# Module_MCU_ArduinoNano.net
KiCad netlist of a schematic drawn in EAGLE
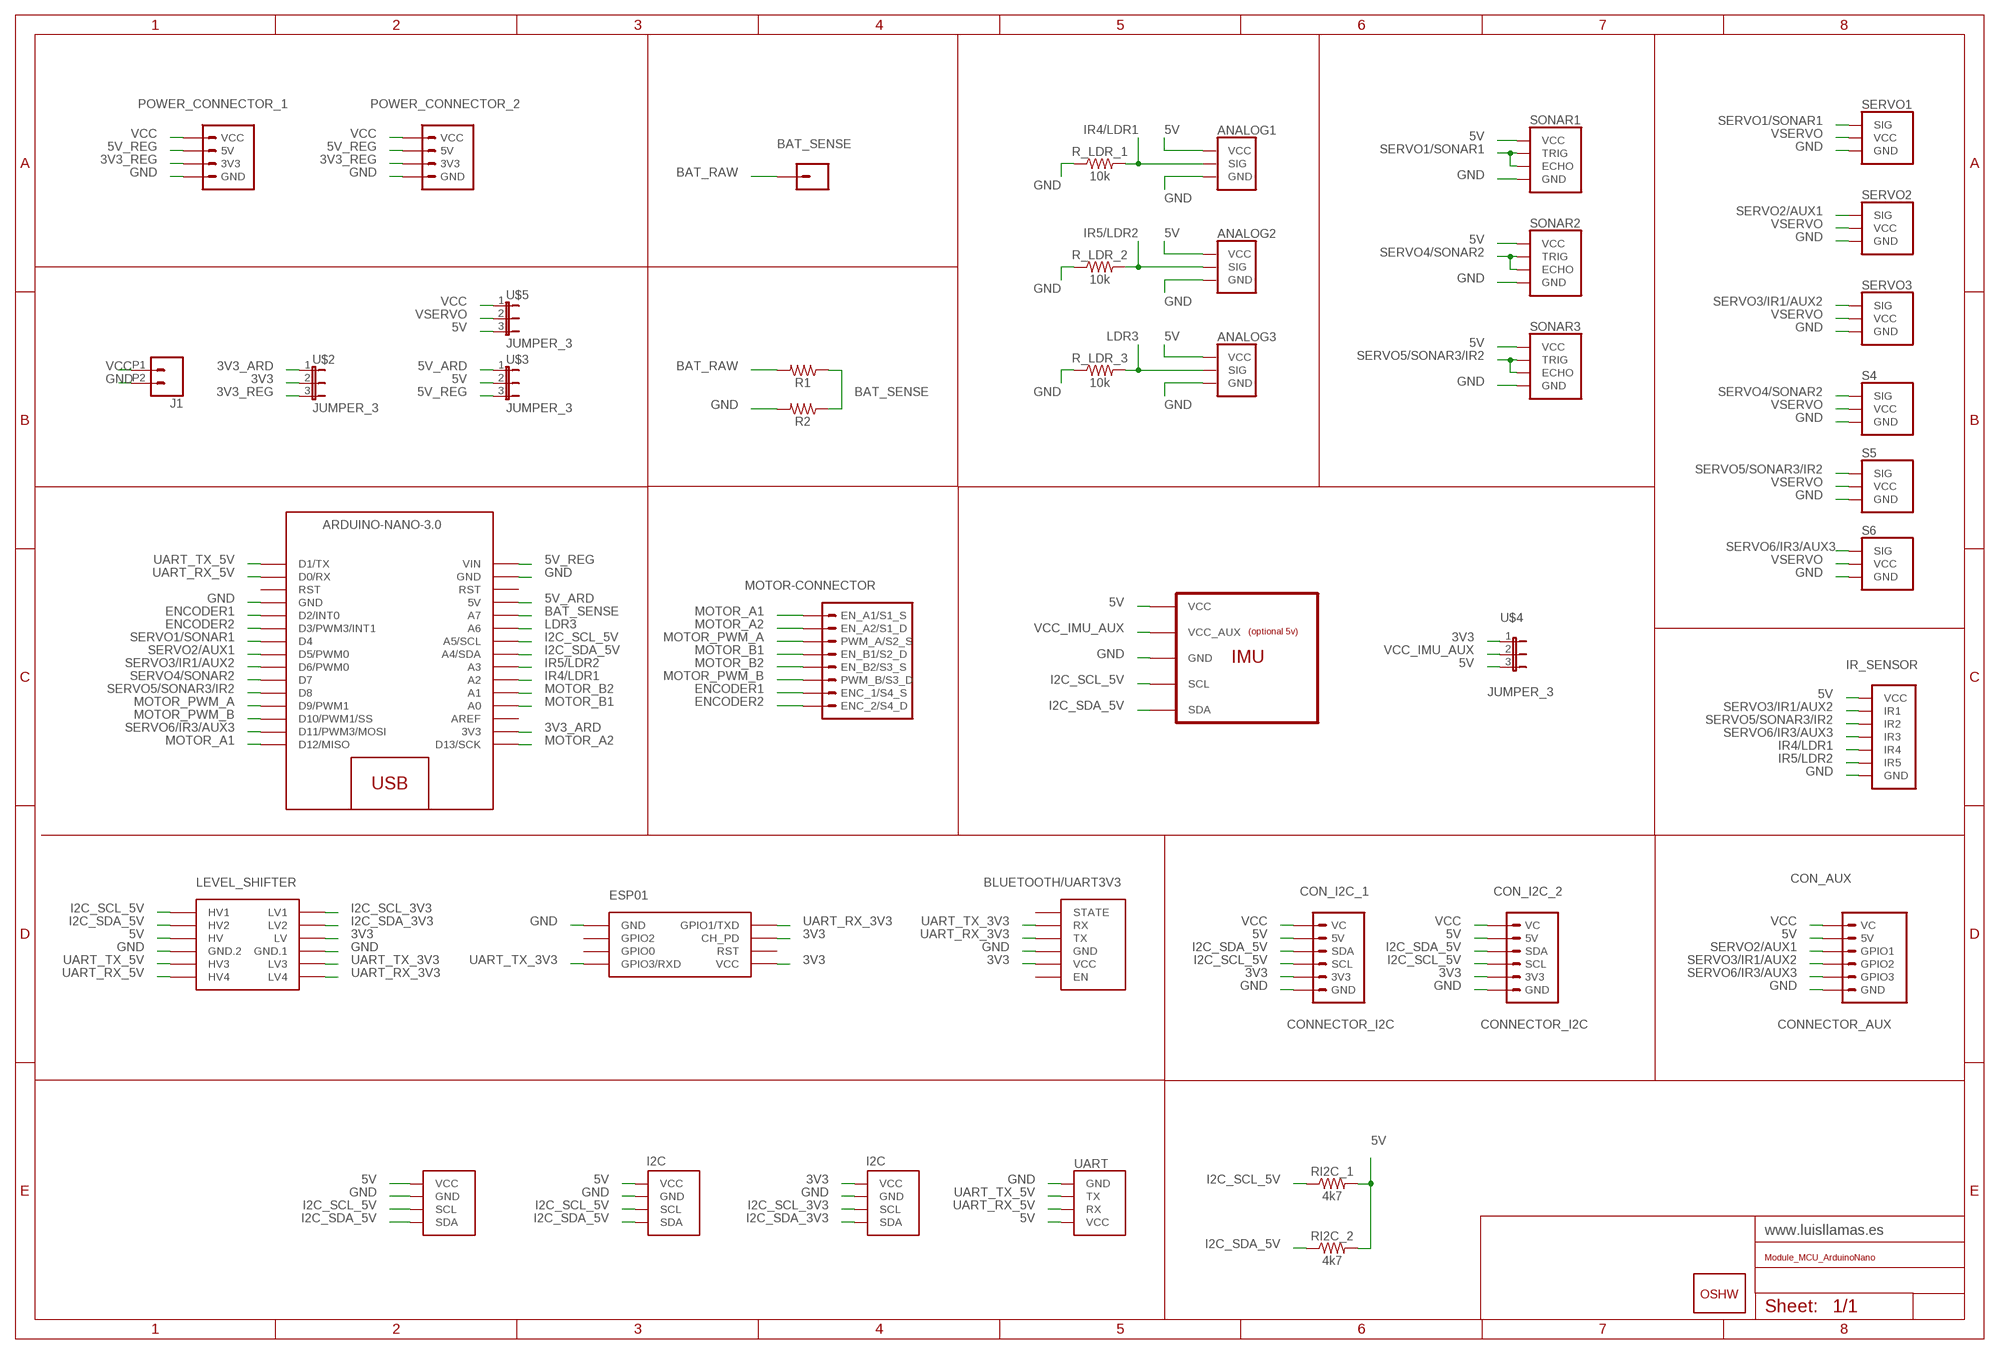
[diagram p0: schematic, sheet 1]

(export (version "E")
  (design (tool "Eeschema 10.0.6"))
  (components
    (comp (ref "ANALOG1")
      (value "LDR/OCT")
      (footprint "eagle-import:LDR")
      (libsource (lib "eagle-import") (part "LDR/OCT"))
    )
    (comp (ref "ANALOG2")
      (value "LDR/OCT")
      (footprint "eagle-import:LDR")
      (libsource (lib "eagle-import") (part "LDR/OCT"))
    )
    (comp (ref "ANALOG3")
      (value "LDR/OCT")
      (footprint "eagle-import:LDR")
      (libsource (lib "eagle-import") (part "LDR/OCT"))
    )
    (comp (ref "ARDUINO_NANO1")
      (value "ARDUINO-NANO-3.0")
      (footprint "eagle-import:ARDUINO-NANO-3.0")
      (libsource (lib "eagle-import") (part "ARDUINO-NANO-3.0"))
    )
    (comp (ref "BAT_SENSE")
      (value "CONN_01")
      (footprint "eagle-import:1X01")
      (libsource (lib "eagle-import") (part "CONN_01"))
    )
    (comp (ref "BLUETOOTH/UART3V3")
      (value "BLUETOOTH-HC-05")
      (footprint "eagle-import:BLUETOOTH-HC-05")
      (libsource (lib "eagle-import") (part "BLUETOOTH-HC-05"))
    )
    (comp (ref "CON_AUX")
      (value "CONNECTOR_AUX")
      (footprint "eagle-import:CONNECTOR_AUX")
      (libsource (lib "eagle-import") (part "CONNECTOR_AUX"))
    )
    (comp (ref "CON_I2C_1")
      (value "CONNECTOR_I2C")
      (footprint "eagle-import:CONNECTOR_I2C")
      (libsource (lib "eagle-import") (part "CONNECTOR_I2C"))
    )
    (comp (ref "CON_I2C_2")
      (value "CONNECTOR_I2C")
      (footprint "eagle-import:CONNECTOR_I2C")
      (libsource (lib "eagle-import") (part "CONNECTOR_I2C"))
    )
    (comp (ref "GOLD_ORB_SM1")
      (value "OSHWLOGO_GOLD_ORB_MED")
      (footprint "eagle-import:OSHW1")
      (libsource (lib "eagle-import") (part "OSHWLOGO_GOLD_ORB_MED"))
    )
    (comp (ref "I2C_1")
      (value "I2C")
      (footprint "eagle-import:I2C_VCC_GND_SCL_SDA")
      (libsource (lib "eagle-import") (part "GENERIC_I2CVCC_GND_SCL_SDA"))
    )
    (comp (ref "I2C_2")
      (value "GENERIC_I2CVCC_GND_SCL_SDA")
      (footprint "eagle-import:I2C_VCC_GND_SCL_SDA")
      (libsource (lib "eagle-import") (part "GENERIC_I2CVCC_GND_SCL_SDA"))
    )
    (comp (ref "I2C_3")
      (value "I2C")
      (footprint "eagle-import:I2C_VCC_GND_SCL_SDA")
      (libsource (lib "eagle-import") (part "GENERIC_I2CVCC_GND_SCL_SDA"))
    )
    (comp (ref "IR_SENSOR")
      (value "IR-5/OCT")
      (footprint "eagle-import:IR-5")
      (libsource (lib "eagle-import") (part "IR-5/OCT"))
    )
    (comp (ref "J1")
      (value "CONN_022.54MM_SCREWTERM")
      (footprint "eagle-import:1X02_2.54_SCREWTERM")
      (libsource (lib "eagle-import") (part "CONN_022.54MM_SCREWTERM"))
    )
    (comp (ref "LEVEL_SHIFTER")
      (value "LEVEL-SHIFTER-4CH")
      (footprint "eagle-import:LEVEL-SHIFTER-4CH")
      (libsource (lib "eagle-import") (part "LEVEL-SHIFTER-4CH"))
    )
    (comp (ref "MOTOR_CONNECTOR")
      (value "MOTOR-CONNECTOR")
      (footprint "eagle-import:MOTOR-CONNECTOR")
      (libsource (lib "eagle-import") (part "MOTOR-CONNECTOR"))
    )
    (comp (ref "POWER_CONNECTOR_1")
      (value "POWER-CONNECTOR")
      (footprint "eagle-import:POWER-CONNECTOR")
      (libsource (lib "eagle-import") (part "POWER-CONNECTOR"))
    )
    (comp (ref "POWER_CONNECTOR_2")
      (value "POWER-CONNECTOR")
      (footprint "eagle-import:POWER-CONNECTOR")
      (libsource (lib "eagle-import") (part "POWER-CONNECTOR"))
    )
    (comp (ref "R1")
      (value "RESISTOR1206")
      (footprint "eagle-import:1206")
      (libsource (lib "eagle-import") (part "RESISTOR1206"))
    )
    (comp (ref "R2")
      (value "RESISTOR1206")
      (footprint "eagle-import:1206")
      (libsource (lib "eagle-import") (part "RESISTOR1206"))
    )
    (comp (ref "RI2C_1")
      (value "4k7")
      (footprint "eagle-import:1206")
      (libsource (lib "eagle-import") (part "RESISTOR1206"))
    )
    (comp (ref "RI2C_2")
      (value "4k7")
      (footprint "eagle-import:1206")
      (libsource (lib "eagle-import") (part "RESISTOR1206"))
    )
    (comp (ref "R_LDR_1")
      (value "10k")
      (footprint "eagle-import:1206")
      (libsource (lib "eagle-import") (part "RESISTOR1206"))
    )
    (comp (ref "R_LDR_2")
      (value "10k")
      (footprint "eagle-import:1206")
      (libsource (lib "eagle-import") (part "RESISTOR1206"))
    )
    (comp (ref "R_LDR_3")
      (value "10k")
      (footprint "eagle-import:1206")
      (libsource (lib "eagle-import") (part "RESISTOR1206"))
    )
    (comp (ref "S4")
      (value "SERVOSERVO")
      (footprint "eagle-import:SERVO")
      (libsource (lib "eagle-import") (part "SERVOSERVO"))
    )
    (comp (ref "S5")
      (value "SERVOSERVO")
      (footprint "eagle-import:SERVO")
      (libsource (lib "eagle-import") (part "SERVOSERVO"))
    )
    (comp (ref "S6")
      (value "SERVOSERVO")
      (footprint "eagle-import:SERVO")
      (libsource (lib "eagle-import") (part "SERVOSERVO"))
    )
    (comp (ref "SERVO1")
      (value "SERVOSERVO")
      (footprint "eagle-import:SERVO")
      (libsource (lib "eagle-import") (part "SERVOSERVO"))
    )
    (comp (ref "SERVO2")
      (value "SERVOSERVO")
      (footprint "eagle-import:SERVO")
      (libsource (lib "eagle-import") (part "SERVOSERVO"))
    )
    (comp (ref "SERVO3")
      (value "SERVOSERVO")
      (footprint "eagle-import:SERVO")
      (libsource (lib "eagle-import") (part "SERVOSERVO"))
    )
    (comp (ref "SONAR1")
      (value "ULTRASONIC/OCT")
      (footprint "eagle-import:ULTRASONIC")
      (libsource (lib "eagle-import") (part "ULTRASONIC/OCT"))
    )
    (comp (ref "SONAR2")
      (value "ULTRASONIC/OCT")
      (footprint "eagle-import:ULTRASONIC")
      (libsource (lib "eagle-import") (part "ULTRASONIC/OCT"))
    )
    (comp (ref "SONAR3")
      (value "ULTRASONIC/OCT")
      (footprint "eagle-import:ULTRASONIC")
      (libsource (lib "eagle-import") (part "ULTRASONIC/OCT"))
    )
    (comp (ref "U$1")
      (value "ESP01")
      (footprint "eagle-import:ESP01")
      (libsource (lib "eagle-import") (part "ESP01"))
    )
    (comp (ref "U$2")
      (value "JUMPER_3")
      (footprint "eagle-import:JUMPER_3")
      (libsource (lib "eagle-import") (part "JUMPER_3"))
    )
    (comp (ref "U$3")
      (value "JUMPER_3")
      (footprint "eagle-import:JUMPER_3")
      (libsource (lib "eagle-import") (part "JUMPER_3"))
    )
    (comp (ref "U$4")
      (value "JUMPER_3")
      (footprint "eagle-import:JUMPER_3")
      (libsource (lib "eagle-import") (part "JUMPER_3"))
    )
    (comp (ref "U$5")
      (value "JUMPER_3")
      (footprint "eagle-import:JUMPER_3")
      (libsource (lib "eagle-import") (part "JUMPER_3"))
    )
    (comp (ref "U1")
      (value "IMU_6/9/10DOFMPU6050")
      (footprint "eagle-import:IMU_6_9_10DOF")
      (libsource (lib "eagle-import") (part "IMU_6/9/10DOFMPU6050"))
    )
    (comp (ref "UART")
      (value "UART")
      (footprint "eagle-import:GENERIC_UART")
      (libsource (lib "eagle-import") (part "GENERIC_UARTGND_TX_RX_VCC"))
    )
  )
  (nets
    (net (code "1") (name "/3V3") (class "Default")
      (node (ref "BLUETOOTH/UART3V3") (pin "VCC") (pinfunction "VCC_VCC") (pintype "power_in"))
      (node (ref "CON_I2C_1") (pin "3V3") (pinfunction "3V3_3V3") (pintype "passive"))
      (node (ref "CON_I2C_2") (pin "3V3") (pinfunction "3V3_3V3") (pintype "passive"))
      (node (ref "I2C_3") (pin "VCC") (pinfunction "VCC_VCC") (pintype "power_in"))
      (node (ref "LEVEL_SHIFTER") (pin "J1.3") (pinfunction "LV_J1.3") (pintype "power_in"))
      (node (ref "U$1") (pin "CH_PD") (pinfunction "CH_PD_CH_PD") (pintype "bidirectional"))
      (node (ref "U$1") (pin "VCC") (pinfunction "VCC_VCC") (pintype "power_in"))
      (node (ref "U$2") (pin "2") (pinfunction "2_2") (pintype "passive"))
      (node (ref "U$4") (pin "1") (pinfunction "1_1") (pintype "passive"))
    )
    (net (code "2") (name "/3V3_ARD") (class "Default")
      (node (ref "ARDUINO_NANO1") (pin "3V3") (pinfunction "3V3_3V3") (pintype "power_in"))
      (node (ref "U$2") (pin "1") (pinfunction "1_1") (pintype "passive"))
    )
    (net (code "3") (name "/3V3_REG") (class "Default")
      (node (ref "POWER_CONNECTOR_1") (pin "3V3") (pinfunction "3V3_3V3") (pintype "passive"))
      (node (ref "POWER_CONNECTOR_2") (pin "3V3") (pinfunction "3V3_3V3") (pintype "passive"))
      (node (ref "U$2") (pin "3") (pinfunction "3_3") (pintype "passive"))
    )
    (net (code "4") (name "/5V") (class "Default")
      (node (ref "ANALOG1") (pin "VCC") (pinfunction "VCC_VCC") (pintype "power_in"))
      (node (ref "ANALOG2") (pin "VCC") (pinfunction "VCC_VCC") (pintype "power_in"))
      (node (ref "ANALOG3") (pin "VCC") (pinfunction "VCC_VCC") (pintype "power_in"))
      (node (ref "CON_AUX") (pin "5V") (pinfunction "5V_5V") (pintype "passive"))
      (node (ref "CON_I2C_1") (pin "5V") (pinfunction "5V_5V") (pintype "passive"))
      (node (ref "CON_I2C_2") (pin "5V") (pinfunction "5V_5V") (pintype "passive"))
      (node (ref "I2C_1") (pin "VCC") (pinfunction "VCC_VCC") (pintype "power_in"))
      (node (ref "I2C_2") (pin "VCC") (pinfunction "VCC_VCC") (pintype "power_in"))
      (node (ref "IR_SENSOR") (pin "VCC") (pinfunction "VCC_VCC") (pintype "power_in"))
      (node (ref "LEVEL_SHIFTER") (pin "J2.3") (pinfunction "HV_J2.3") (pintype "power_in"))
      (node (ref "RI2C_1") (pin "2") (pinfunction "2_2") (pintype "passive"))
      (node (ref "RI2C_2") (pin "2") (pinfunction "2_2") (pintype "passive"))
      (node (ref "SONAR1") (pin "VCC") (pinfunction "VCC_VCC") (pintype "power_in"))
      (node (ref "SONAR2") (pin "VCC") (pinfunction "VCC_VCC") (pintype "power_in"))
      (node (ref "SONAR3") (pin "VCC") (pinfunction "VCC_VCC") (pintype "power_in"))
      (node (ref "U$3") (pin "2") (pinfunction "2_2") (pintype "passive"))
      (node (ref "U$4") (pin "3") (pinfunction "3_3") (pintype "passive"))
      (node (ref "U$5") (pin "3") (pinfunction "3_3") (pintype "passive"))
      (node (ref "U1") (pin "VCC") (pinfunction "VCC_VCC") (pintype "power_in"))
      (node (ref "UART") (pin "VCC") (pinfunction "VCC_VCC") (pintype "bidirectional"))
    )
    (net (code "5") (name "/5V_ARD") (class "Default")
      (node (ref "ARDUINO_NANO1") (pin "5V") (pinfunction "5V_5V") (pintype "bidirectional"))
      (node (ref "U$3") (pin "1") (pinfunction "1_1") (pintype "passive"))
    )
    (net (code "6") (name "/5V_REG") (class "Default")
      (node (ref "ARDUINO_NANO1") (pin "VIN") (pinfunction "VIN_VIN") (pintype "power_in"))
      (node (ref "POWER_CONNECTOR_1") (pin "5V") (pinfunction "5V_5V") (pintype "passive"))
      (node (ref "POWER_CONNECTOR_2") (pin "5V") (pinfunction "5V_5V") (pintype "passive"))
      (node (ref "U$3") (pin "3") (pinfunction "3_3") (pintype "passive"))
    )
    (net (code "7") (name "/BAT_RAW") (class "Default")
      (node (ref "BAT_SENSE") (pin "1") (pinfunction "1_1") (pintype "passive"))
      (node (ref "R1") (pin "2") (pinfunction "2_2") (pintype "passive"))
    )
    (net (code "8") (name "/BAT_SENSE") (class "Default")
      (node (ref "ARDUINO_NANO1") (pin "A7") (pinfunction "A7_A7") (pintype "bidirectional"))
      (node (ref "R1") (pin "1") (pinfunction "1_1") (pintype "passive"))
      (node (ref "R2") (pin "1") (pinfunction "1_1") (pintype "passive"))
    )
    (net (code "9") (name "/ENCODER1") (class "Default")
      (node (ref "ARDUINO_NANO1") (pin "D2") (pinfunction "D2/INT0_D2") (pintype "bidirectional"))
      (node (ref "MOTOR_CONNECTOR") (pin "ENC_1/S4_S") (pinfunction "ENC_1/S4_S_ENC_1/S4_S") (pintype "passive"))
    )
    (net (code "10") (name "/ENCODER2") (class "Default")
      (node (ref "ARDUINO_NANO1") (pin "D3") (pinfunction "D3/PWM3/INT1_D3") (pintype "bidirectional"))
      (node (ref "MOTOR_CONNECTOR") (pin "ENC_2/S4_D") (pinfunction "ENC_2/S4_D_ENC_2/S4_D") (pintype "passive"))
    )
    (net (code "11") (name "/GND") (class "Default")
      (node (ref "ANALOG1") (pin "GND") (pinfunction "GND_GND") (pintype "power_in"))
      (node (ref "ANALOG2") (pin "GND") (pinfunction "GND_GND") (pintype "power_in"))
      (node (ref "ANALOG3") (pin "GND") (pinfunction "GND_GND") (pintype "power_in"))
      (node (ref "ARDUINO_NANO1") (pin "GND@1") (pinfunction "GND_GND@1") (pintype "power_in"))
      (node (ref "ARDUINO_NANO1") (pin "GND@2") (pinfunction "GND_GND@2") (pintype "power_in"))
      (node (ref "BLUETOOTH/UART3V3") (pin "GND") (pinfunction "GND_GND") (pintype "power_in"))
      (node (ref "CON_AUX") (pin "GND") (pinfunction "GND_GND") (pintype "passive"))
      (node (ref "CON_I2C_1") (pin "GND") (pinfunction "GND_GND") (pintype "passive"))
      (node (ref "CON_I2C_2") (pin "GND") (pinfunction "GND_GND") (pintype "passive"))
      (node (ref "I2C_1") (pin "GND") (pinfunction "GND_GND") (pintype "power_in"))
      (node (ref "I2C_2") (pin "GND") (pinfunction "GND_GND") (pintype "power_in"))
      (node (ref "I2C_3") (pin "GND") (pinfunction "GND_GND") (pintype "power_in"))
      (node (ref "IR_SENSOR") (pin "GND") (pinfunction "GND_GND") (pintype "power_in"))
      (node (ref "J1") (pin "P2") (pinfunction "2_P2") (pintype "passive"))
      (node (ref "LEVEL_SHIFTER") (pin "J1.4") (pinfunction "GND.1_J1.4") (pintype "power_in"))
      (node (ref "LEVEL_SHIFTER") (pin "J2.4") (pinfunction "GND.2_J2.4") (pintype "power_in"))
      (node (ref "POWER_CONNECTOR_1") (pin "GND") (pinfunction "GND_GND") (pintype "passive"))
      (node (ref "POWER_CONNECTOR_2") (pin "GND") (pinfunction "GND_GND") (pintype "passive"))
      (node (ref "R2") (pin "2") (pinfunction "2_2") (pintype "passive"))
      (node (ref "R_LDR_1") (pin "1") (pinfunction "1_1") (pintype "passive"))
      (node (ref "R_LDR_2") (pin "1") (pinfunction "1_1") (pintype "passive"))
      (node (ref "R_LDR_3") (pin "1") (pinfunction "1_1") (pintype "passive"))
      (node (ref "S4") (pin "GND") (pinfunction "GND_GND") (pintype "power_in"))
      (node (ref "S5") (pin "GND") (pinfunction "GND_GND") (pintype "power_in"))
      (node (ref "S6") (pin "GND") (pinfunction "GND_GND") (pintype "power_in"))
      (node (ref "SERVO1") (pin "GND") (pinfunction "GND_GND") (pintype "power_in"))
      (node (ref "SERVO2") (pin "GND") (pinfunction "GND_GND") (pintype "power_in"))
      (node (ref "SERVO3") (pin "GND") (pinfunction "GND_GND") (pintype "power_in"))
      (node (ref "SONAR1") (pin "GND") (pinfunction "GND_GND") (pintype "power_in"))
      (node (ref "SONAR2") (pin "GND") (pinfunction "GND_GND") (pintype "power_in"))
      (node (ref "SONAR3") (pin "GND") (pinfunction "GND_GND") (pintype "power_in"))
      (node (ref "U$1") (pin "GND") (pinfunction "GND_GND") (pintype "power_in"))
      (node (ref "U1") (pin "GND") (pinfunction "GND_GND") (pintype "power_in"))
      (node (ref "UART") (pin "GND") (pinfunction "GND_GND") (pintype "power_in"))
    )
    (net (code "12") (name "/I2C_SCL_3V3") (class "Default")
      (node (ref "I2C_3") (pin "SCL") (pinfunction "SCL_SCL") (pintype "bidirectional"))
      (node (ref "LEVEL_SHIFTER") (pin "J1.1") (pinfunction "LV1_J1.1") (pintype "bidirectional"))
    )
    (net (code "13") (name "/I2C_SCL_5V") (class "Default")
      (node (ref "ARDUINO_NANO1") (pin "A5") (pinfunction "A5/SCL_A5") (pintype "bidirectional"))
      (node (ref "CON_I2C_1") (pin "SCL") (pinfunction "SCL_SCL") (pintype "passive"))
      (node (ref "CON_I2C_2") (pin "SCL") (pinfunction "SCL_SCL") (pintype "passive"))
      (node (ref "I2C_1") (pin "SCL") (pinfunction "SCL_SCL") (pintype "bidirectional"))
      (node (ref "I2C_2") (pin "SCL") (pinfunction "SCL_SCL") (pintype "bidirectional"))
      (node (ref "LEVEL_SHIFTER") (pin "J2.1") (pinfunction "HV1_J2.1") (pintype "bidirectional"))
      (node (ref "RI2C_1") (pin "1") (pinfunction "1_1") (pintype "passive"))
      (node (ref "U1") (pin "SCL") (pinfunction "SCL_SCL") (pintype "bidirectional"))
    )
    (net (code "14") (name "/I2C_SDA_3V3") (class "Default")
      (node (ref "I2C_3") (pin "SDA") (pinfunction "SDA_SDA") (pintype "bidirectional"))
      (node (ref "LEVEL_SHIFTER") (pin "J1.2") (pinfunction "LV2_J1.2") (pintype "bidirectional"))
    )
    (net (code "15") (name "/I2C_SDA_5V") (class "Default")
      (node (ref "ARDUINO_NANO1") (pin "A4") (pinfunction "A4/SDA_A4") (pintype "bidirectional"))
      (node (ref "CON_I2C_1") (pin "SDA") (pinfunction "SDA_SDA") (pintype "passive"))
      (node (ref "CON_I2C_2") (pin "SDA") (pinfunction "SDA_SDA") (pintype "passive"))
      (node (ref "I2C_1") (pin "SDA") (pinfunction "SDA_SDA") (pintype "bidirectional"))
      (node (ref "I2C_2") (pin "SDA") (pinfunction "SDA_SDA") (pintype "bidirectional"))
      (node (ref "LEVEL_SHIFTER") (pin "J2.2") (pinfunction "HV2_J2.2") (pintype "bidirectional"))
      (node (ref "RI2C_2") (pin "1") (pinfunction "1_1") (pintype "passive"))
      (node (ref "U1") (pin "SDA") (pinfunction "SDA_SDA") (pintype "bidirectional"))
    )
    (net (code "16") (name "/IR4{slash}LDR1") (class "Default")
      (node (ref "ANALOG1") (pin "SIG") (pinfunction "SIG_SIG") (pintype "bidirectional"))
      (node (ref "ARDUINO_NANO1") (pin "A2") (pinfunction "A2_A2") (pintype "bidirectional"))
      (node (ref "IR_SENSOR") (pin "4") (pinfunction "IR4_4") (pintype "bidirectional"))
      (node (ref "R_LDR_1") (pin "2") (pinfunction "2_2") (pintype "passive"))
    )
    (net (code "17") (name "/IR5{slash}LDR2") (class "Default")
      (node (ref "ANALOG2") (pin "SIG") (pinfunction "SIG_SIG") (pintype "bidirectional"))
      (node (ref "ARDUINO_NANO1") (pin "A3") (pinfunction "A3_A3") (pintype "bidirectional"))
      (node (ref "IR_SENSOR") (pin "5") (pinfunction "IR5_5") (pintype "bidirectional"))
      (node (ref "R_LDR_2") (pin "2") (pinfunction "2_2") (pintype "passive"))
    )
    (net (code "18") (name "/LDR3") (class "Default")
      (node (ref "ANALOG3") (pin "SIG") (pinfunction "SIG_SIG") (pintype "bidirectional"))
      (node (ref "ARDUINO_NANO1") (pin "A6") (pinfunction "A6_A6") (pintype "bidirectional"))
      (node (ref "R_LDR_3") (pin "2") (pinfunction "2_2") (pintype "passive"))
    )
    (net (code "19") (name "/MOTOR_A1") (class "Default")
      (node (ref "ARDUINO_NANO1") (pin "D12") (pinfunction "D12/MISO_D12") (pintype "bidirectional"))
      (node (ref "MOTOR_CONNECTOR") (pin "EN_A1/S1_S") (pinfunction "EN_A1/S1_S_EN_A1/S1_S") (pintype "passive"))
    )
    (net (code "20") (name "/MOTOR_A2") (class "Default")
      (node (ref "ARDUINO_NANO1") (pin "D13") (pinfunction "D13/SCK_D13") (pintype "bidirectional"))
      (node (ref "MOTOR_CONNECTOR") (pin "EN_A2/S1_D") (pinfunction "EN_A2/S1_D_EN_A2/S1_D") (pintype "passive"))
    )
    (net (code "21") (name "/MOTOR_B1") (class "Default")
      (node (ref "ARDUINO_NANO1") (pin "A0") (pinfunction "A0_A0") (pintype "bidirectional"))
      (node (ref "MOTOR_CONNECTOR") (pin "EN_B1/S2_D") (pinfunction "EN_B1/S2_D_EN_B1/S2_D") (pintype "passive"))
    )
    (net (code "22") (name "/MOTOR_B2") (class "Default")
      (node (ref "ARDUINO_NANO1") (pin "A1") (pinfunction "A1_A1") (pintype "bidirectional"))
      (node (ref "MOTOR_CONNECTOR") (pin "EN_B2/S3_S") (pinfunction "EN_B2/S3_S_EN_B2/S3_S") (pintype "passive"))
    )
    (net (code "23") (name "/MOTOR_PWM_A") (class "Default")
      (node (ref "ARDUINO_NANO1") (pin "D9") (pinfunction "D9/PWM1_D9") (pintype "bidirectional"))
      (node (ref "MOTOR_CONNECTOR") (pin "PWM_A/S2_S") (pinfunction "PWM_A/S2_S_PWM_A/S2_S") (pintype "passive"))
    )
    (net (code "24") (name "/MOTOR_PWM_B") (class "Default")
      (node (ref "ARDUINO_NANO1") (pin "D10") (pinfunction "D10/PWM1/SS_D10") (pintype "bidirectional"))
      (node (ref "MOTOR_CONNECTOR") (pin "PWM_B/S3_D") (pinfunction "PWM_B/S3_D_PWM_B/S3_D") (pintype "passive"))
    )
    (net (code "25") (name "/SERVO1{slash}SONAR1") (class "Default")
      (node (ref "ARDUINO_NANO1") (pin "D4") (pinfunction "D4_D4") (pintype "bidirectional"))
      (node (ref "SERVO1") (pin "SIG") (pinfunction "SIG_SIG") (pintype "bidirectional"))
      (node (ref "SONAR1") (pin "ECHO") (pinfunction "ECHO_ECHO") (pintype "bidirectional"))
      (node (ref "SONAR1") (pin "TRIG") (pinfunction "TRIG_TRIG") (pintype "bidirectional"))
    )
    (net (code "26") (name "/SERVO2{slash}AUX1") (class "Default")
      (node (ref "ARDUINO_NANO1") (pin "D5") (pinfunction "D5/PWM0_D5") (pintype "bidirectional"))
      (node (ref "CON_AUX") (pin "GPIO1") (pinfunction "GPIO1_GPIO1") (pintype "passive"))
      (node (ref "SERVO2") (pin "SIG") (pinfunction "SIG_SIG") (pintype "bidirectional"))
    )
    (net (code "27") (name "/SERVO3{slash}IR1{slash}AUX2") (class "Default")
      (node (ref "ARDUINO_NANO1") (pin "D6") (pinfunction "D6/PWM0_D6") (pintype "bidirectional"))
      (node (ref "CON_AUX") (pin "GPIO2") (pinfunction "GPIO2_GPIO2") (pintype "passive"))
      (node (ref "IR_SENSOR") (pin "1") (pinfunction "IR1_1") (pintype "bidirectional"))
      (node (ref "SERVO3") (pin "SIG") (pinfunction "SIG_SIG") (pintype "bidirectional"))
    )
    (net (code "28") (name "/SERVO4{slash}SONAR2") (class "Default")
      (node (ref "ARDUINO_NANO1") (pin "D7") (pinfunction "D7_D7") (pintype "bidirectional"))
      (node (ref "S4") (pin "SIG") (pinfunction "SIG_SIG") (pintype "bidirectional"))
      (node (ref "SONAR2") (pin "ECHO") (pinfunction "ECHO_ECHO") (pintype "bidirectional"))
      (node (ref "SONAR2") (pin "TRIG") (pinfunction "TRIG_TRIG") (pintype "bidirectional"))
    )
    (net (code "29") (name "/SERVO5{slash}SONAR3{slash}IR2") (class "Default")
      (node (ref "ARDUINO_NANO1") (pin "D8") (pinfunction "D8_D8") (pintype "bidirectional"))
      (node (ref "IR_SENSOR") (pin "2") (pinfunction "IR2_2") (pintype "bidirectional"))
      (node (ref "S5") (pin "SIG") (pinfunction "SIG_SIG") (pintype "bidirectional"))
      (node (ref "SONAR3") (pin "ECHO") (pinfunction "ECHO_ECHO") (pintype "bidirectional"))
      (node (ref "SONAR3") (pin "TRIG") (pinfunction "TRIG_TRIG") (pintype "bidirectional"))
    )
    (net (code "30") (name "/SERVO6{slash}IR3{slash}AUX3") (class "Default")
      (node (ref "ARDUINO_NANO1") (pin "D11") (pinfunction "D11/PWM3/MOSI_D11") (pintype "bidirectional"))
      (node (ref "CON_AUX") (pin "GPIO3") (pinfunction "GPIO3_GPIO3") (pintype "passive"))
      (node (ref "IR_SENSOR") (pin "3") (pinfunction "IR3_3") (pintype "bidirectional"))
      (node (ref "S6") (pin "SIG") (pinfunction "SIG_SIG") (pintype "bidirectional"))
    )
    (net (code "31") (name "/UART_RX_3V3") (class "Default")
      (node (ref "BLUETOOTH/UART3V3") (pin "TX") (pinfunction "TX_TX") (pintype "bidirectional"))
      (node (ref "LEVEL_SHIFTER") (pin "J1.6") (pinfunction "LV4_J1.6") (pintype "bidirectional"))
      (node (ref "U$1") (pin "TX") (pinfunction "GPIO1/TXD_TX") (pintype "bidirectional"))
    )
    (net (code "32") (name "/UART_RX_5V") (class "Default")
      (node (ref "ARDUINO_NANO1") (pin "RX0") (pinfunction "D0/RX_RX0") (pintype "bidirectional"))
      (node (ref "LEVEL_SHIFTER") (pin "J2.6") (pinfunction "HV4_J2.6") (pintype "bidirectional"))
      (node (ref "UART") (pin "RX") (pinfunction "RX_RX") (pintype "bidirectional"))
    )
    (net (code "33") (name "/UART_TX_3V3") (class "Default")
      (node (ref "BLUETOOTH/UART3V3") (pin "RX") (pinfunction "RX_RX") (pintype "bidirectional"))
      (node (ref "LEVEL_SHIFTER") (pin "J1.5") (pinfunction "LV3_J1.5") (pintype "bidirectional"))
      (node (ref "U$1") (pin "RX") (pinfunction "GPIO3/RXD_RX") (pintype "bidirectional"))
    )
    (net (code "34") (name "/UART_TX_5V") (class "Default")
      (node (ref "ARDUINO_NANO1") (pin "TX1") (pinfunction "D1/TX_TX1") (pintype "bidirectional"))
      (node (ref "LEVEL_SHIFTER") (pin "J2.5") (pinfunction "HV3_J2.5") (pintype "bidirectional"))
      (node (ref "UART") (pin "TX") (pinfunction "TX_TX") (pintype "power_in"))
    )
    (net (code "35") (name "/VCC") (class "Default")
      (node (ref "CON_AUX") (pin "VC") (pinfunction "VC_VC") (pintype "passive"))
      (node (ref "CON_I2C_1") (pin "VC") (pinfunction "VC_VC") (pintype "passive"))
      (node (ref "CON_I2C_2") (pin "VC") (pinfunction "VC_VC") (pintype "passive"))
      (node (ref "J1") (pin "P1") (pinfunction "1_P1") (pintype "passive"))
      (node (ref "POWER_CONNECTOR_1") (pin "VCC") (pinfunction "VCC_VCC") (pintype "passive"))
      (node (ref "POWER_CONNECTOR_2") (pin "VCC") (pinfunction "VCC_VCC") (pintype "passive"))
      (node (ref "U$5") (pin "1") (pinfunction "1_1") (pintype "passive"))
    )
    (net (code "36") (name "/VCC_IMU_AUX") (class "Default")
      (node (ref "U$4") (pin "2") (pinfunction "2_2") (pintype "passive"))
      (node (ref "U1") (pin "VCC_AUX") (pinfunction "VCC_AUX_VCC_AUX") (pintype "power_in"))
    )
    (net (code "37") (name "/VSERVO") (class "Default")
      (node (ref "S4") (pin "VCC") (pinfunction "VCC_VCC") (pintype "power_in"))
      (node (ref "S5") (pin "VCC") (pinfunction "VCC_VCC") (pintype "power_in"))
      (node (ref "S6") (pin "VCC") (pinfunction "VCC_VCC") (pintype "power_in"))
      (node (ref "SERVO1") (pin "VCC") (pinfunction "VCC_VCC") (pintype "power_in"))
      (node (ref "SERVO2") (pin "VCC") (pinfunction "VCC_VCC") (pintype "power_in"))
      (node (ref "SERVO3") (pin "VCC") (pinfunction "VCC_VCC") (pintype "power_in"))
      (node (ref "U$5") (pin "2") (pinfunction "2_2") (pintype "passive"))
    )
    (net (code "38") (name "unconnected-(ARDUINO_NANO1-AREF-PadREG)") (class "Default")
      (node (ref "ARDUINO_NANO1") (pin "REG") (pinfunction "AREF_REG") (pintype "bidirectional"))
    )
    (net (code "39") (name "unconnected-(ARDUINO_NANO1-RST-PadRST@1)") (class "Default")
      (node (ref "ARDUINO_NANO1") (pin "RST@1") (pinfunction "RST_RST@1") (pintype "bidirectional"))
    )
    (net (code "40") (name "unconnected-(ARDUINO_NANO1-RST-PadRST@2)") (class "Default")
      (node (ref "ARDUINO_NANO1") (pin "RST@2") (pinfunction "RST_RST@2") (pintype "bidirectional"))
    )
    (net (code "41") (name "unconnected-(BLUETOOTH/UART3V3-PadEN)") (class "Default")
      (node (ref "BLUETOOTH/UART3V3") (pin "EN") (pinfunction "EN_EN") (pintype "bidirectional"))
    )
    (net (code "42") (name "unconnected-(BLUETOOTH/UART3V3-PadSTATE)") (class "Default")
      (node (ref "BLUETOOTH/UART3V3") (pin "STATE") (pinfunction "STATE_STATE") (pintype "bidirectional"))
    )
    (net (code "43") (name "unconnected-(U$1-PadGPIO0)") (class "Default")
      (node (ref "U$1") (pin "GPIO0") (pinfunction "GPIO0_GPIO0") (pintype "bidirectional"))
    )
    (net (code "44") (name "unconnected-(U$1-PadGPIO2)") (class "Default")
      (node (ref "U$1") (pin "GPIO2") (pinfunction "GPIO2_GPIO2") (pintype "bidirectional"))
    )
    (net (code "45") (name "unconnected-(U$1-PadRST)") (class "Default")
      (node (ref "U$1") (pin "RST") (pinfunction "RST_RST") (pintype "bidirectional"))
    )
  )
)
